# Connector.net
KiCad netlist of a schematic drawn in Altium Designer
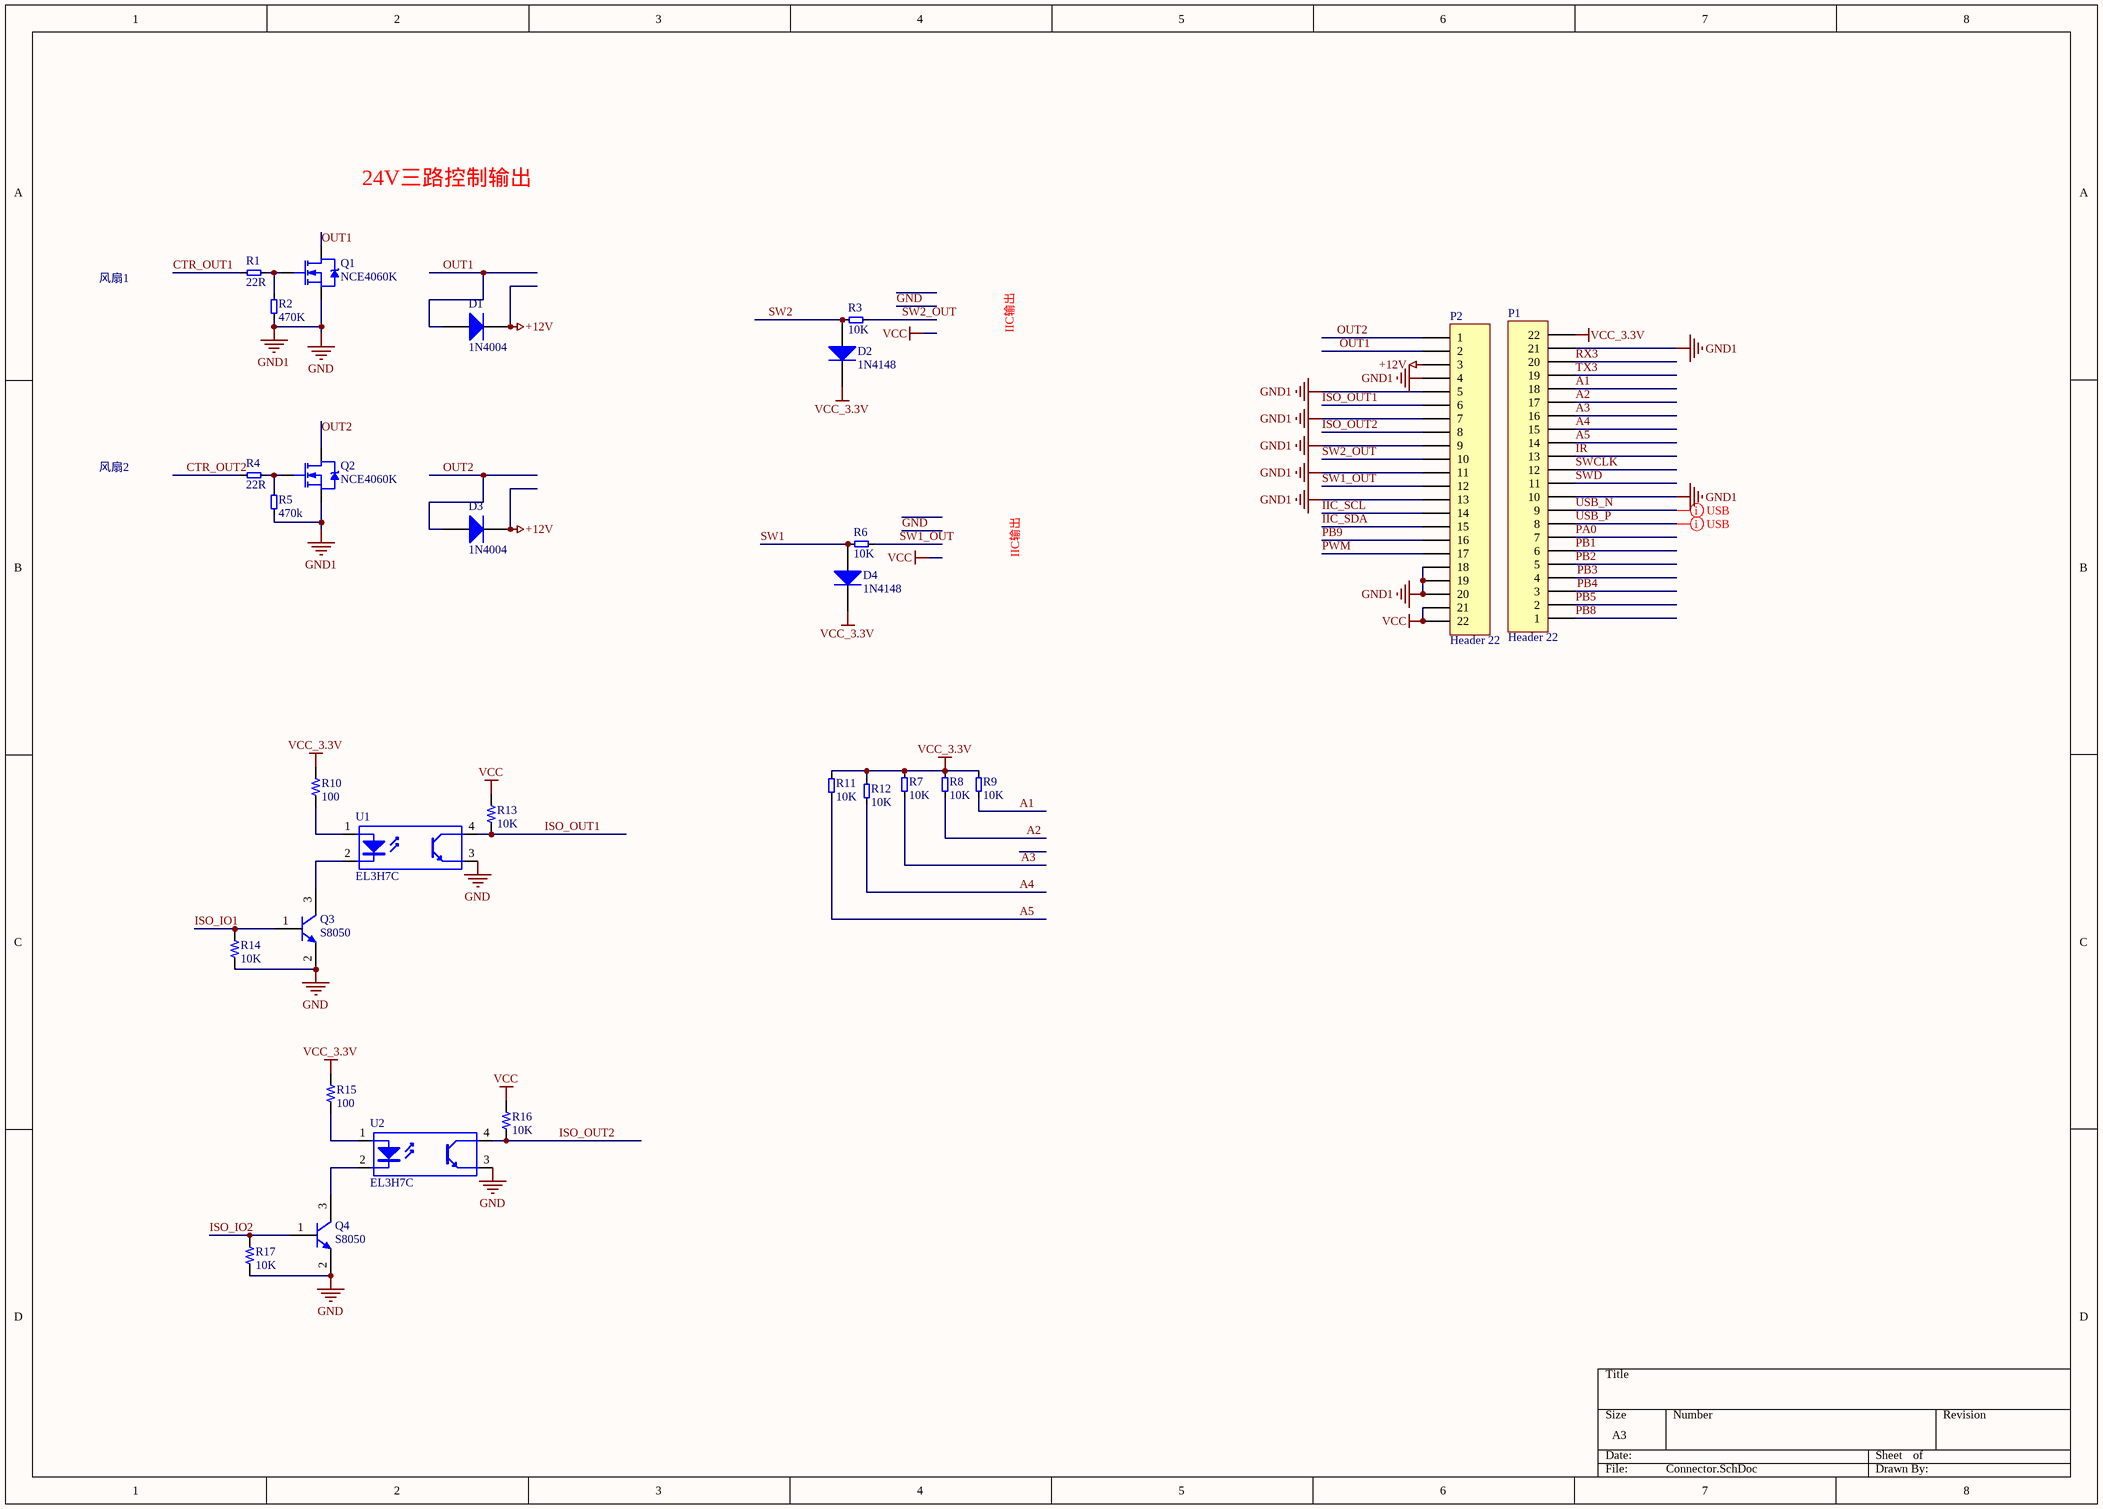
[diagram p0: Connector.SchDoc]

(export (version "E")
  (design (tool "Eeschema 10.0.6"))
  (components
    (comp (ref "D1")
      (value "1N4004")
      (footprint "SMA")
      (description "Default Diode")
      (fields (field (name "PUBLISHER") "Altium Limited"))
      (libsource (lib "SM") (part "Diode_2"))
    )
    (comp (ref "D2")
      (value "1N4148")
      (footprint "sod323")
      (description "Default Diode")
      (fields (field (name "PUBLISHER") "Altium Limited"))
      (libsource (lib "Miscellaneous Devices") (part "Diode"))
    )
    (comp (ref "D3")
      (value "1N4004")
      (footprint "SMA")
      (description "Default Diode")
      (fields (field (name "PUBLISHER") "Altium Limited"))
      (libsource (lib "SM") (part "Diode_2"))
    )
    (comp (ref "D4")
      (value "1N4148")
      (footprint "sod323")
      (description "Default Diode")
      (fields (field (name "PUBLISHER") "Altium Limited"))
      (libsource (lib "Miscellaneous Devices") (part "Diode"))
    )
    (comp (ref "P1")
      (value "Header 22")
      (footprint "pcb_module_a")
      (description "Header, 22-Pin")
      (fields (field (name "PUBLISHER") "Altium Limited"))
      (libsource (lib "Miscellaneous Connectors") (part "Header 22"))
    )
    (comp (ref "P2")
      (value "Header 22")
      (footprint "pcb_module_a")
      (description "Header, 22-Pin")
      (fields (field (name "PUBLISHER") "Altium Limited"))
      (libsource (lib "") (part "Header 22_1"))
    )
    (comp (ref "Q1")
      (value "NCE4060K")
      (footprint "TO-252-3S")
      (description "NMOSFET")
      (libsource (lib "SM") (part "NCE4060K"))
    )
    (comp (ref "Q2")
      (value "NCE4060K")
      (footprint "TO-252-3S")
      (description "NMOSFET")
      (libsource (lib "SM") (part "NCE4060K"))
    )
    (comp (ref "Q3") (value "S8050") (footprint "SOT23-3") (libsource (lib "Schlib1") (part "NPN")))
    (comp (ref "Q4") (value "S8050") (footprint "SOT23-3") (libsource (lib "Schlib1") (part "NPN")))
    (comp (ref "R1")
      (value "22R")
      (footprint "0402R")
      (description "CR85-102J")
      (libsource (lib "SMD电阻") (part "1K"))
    )
    (comp (ref "R2")
      (value "470K")
      (footprint "0402R")
      (description "CR85-102J")
      (libsource (lib "SMD电阻") (part "1K"))
    )
    (comp (ref "R3")
      (value "10K")
      (footprint "0402R")
      (description "CR85-102J")
      (libsource (lib "SMD电阻") (part "1K"))
    )
    (comp (ref "R4")
      (value "22R")
      (footprint "0402R")
      (description "CR85-102J")
      (libsource (lib "SMD电阻") (part "1K"))
    )
    (comp (ref "R5")
      (value "470k")
      (footprint "0402R")
      (description "CR85-102J")
      (libsource (lib "SMD电阻") (part "1K"))
    )
    (comp (ref "R6")
      (value "10K")
      (footprint "0402R")
      (description "CR85-102J")
      (libsource (lib "SMD电阻") (part "1K"))
    )
    (comp (ref "R7")
      (value "10K")
      (footprint "0402R")
      (description "CR85-102J")
      (libsource (lib "SMD电阻") (part "1K"))
    )
    (comp (ref "R8")
      (value "10K")
      (footprint "0402R")
      (description "CR85-102J")
      (libsource (lib "SMD电阻") (part "1K"))
    )
    (comp (ref "R9")
      (value "10K")
      (footprint "0402R")
      (description "CR85-102J")
      (libsource (lib "SMD电阻") (part "1K"))
    )
    (comp (ref "R10")
      (value "100")
      (footprint "0402R")
      (description "R")
      (libsource (lib "JRJ_1") (part "R"))
    )
    (comp (ref "R11")
      (value "10K")
      (footprint "0402R")
      (description "CR85-102J")
      (libsource (lib "SMD电阻") (part "1K"))
    )
    (comp (ref "R12")
      (value "10K")
      (footprint "0402R")
      (description "CR85-102J")
      (libsource (lib "SMD电阻") (part "1K"))
    )
    (comp (ref "R13")
      (value "10K")
      (footprint "0402R")
      (description "R")
      (libsource (lib "JRJ_1") (part "R"))
    )
    (comp (ref "R14")
      (value "10K")
      (footprint "0402R")
      (description "R")
      (libsource (lib "JRJ_1") (part "R"))
    )
    (comp (ref "R15")
      (value "100")
      (footprint "0402R")
      (description "R")
      (libsource (lib "JRJ_1") (part "R"))
    )
    (comp (ref "R16")
      (value "10K")
      (footprint "0402R")
      (description "R")
      (libsource (lib "JRJ_1") (part "R"))
    )
    (comp (ref "R17")
      (value "10K")
      (footprint "0402R")
      (description "R")
      (libsource (lib "JRJ_1") (part "R"))
    )
    (comp (ref "U1")
      (value "EL3H7C")
      (footprint "EL3H7C")
      (description "4-Pin Phototransistor Optocoupler")
      (fields (field (name "PUBLISHER") "Altium Limited"))
      (libsource (lib "Miscellaneous Devices") (part "Optoisolator1"))
    )
    (comp (ref "U2")
      (value "EL3H7C")
      (footprint "EL3H7C")
      (description "4-Pin Phototransistor Optocoupler")
      (fields (field (name "PUBLISHER") "Altium Limited"))
      (libsource (lib "Miscellaneous Devices") (part "Optoisolator1"))
    )
  )
  (nets
    (net (code "1") (name "+12V") (class "Default")
      (node (ref "D1") (pin "2") (pinfunction "K_2") (pintype "passive"))
      (node (ref "D3") (pin "2") (pinfunction "K_2") (pintype "passive"))
      (node (ref "P2") (pin "3") (pinfunction "3_3") (pintype "passive"))
    )
    (net (code "2") (name "/A1") (class "Default")
      (node (ref "P1") (pin "18") (pinfunction "18_18") (pintype "passive"))
      (node (ref "R9") (pin "1") (pinfunction "1_1") (pintype "passive"))
    )
    (net (code "3") (name "/A2") (class "Default")
      (node (ref "P1") (pin "17") (pinfunction "17_17") (pintype "passive"))
      (node (ref "R8") (pin "1") (pinfunction "1_1") (pintype "passive"))
    )
    (net (code "4") (name "/A3") (class "Default")
      (node (ref "P1") (pin "16") (pinfunction "16_16") (pintype "passive"))
      (node (ref "R7") (pin "1") (pinfunction "1_1") (pintype "passive"))
    )
    (net (code "5") (name "/A4") (class "Default")
      (node (ref "P1") (pin "15") (pinfunction "15_15") (pintype "passive"))
      (node (ref "R12") (pin "2") (pinfunction "2_2") (pintype "passive"))
    )
    (net (code "6") (name "/A5") (class "Default")
      (node (ref "P1") (pin "14") (pinfunction "14_14") (pintype "passive"))
      (node (ref "R11") (pin "1") (pinfunction "1_1") (pintype "passive"))
    )
    (net (code "7") (name "/CTR_OUT1") (class "Default")
      (node (ref "R1") (pin "1") (pinfunction "1_1") (pintype "passive"))
    )
    (net (code "8") (name "/CTR_OUT2") (class "Default")
      (node (ref "R4") (pin "1") (pinfunction "1_1") (pintype "passive"))
    )
    (net (code "9") (name "/IIC_SCL") (class "Default")
      (node (ref "P2") (pin "14") (pinfunction "14_14") (pintype "passive"))
    )
    (net (code "10") (name "/IIC_SDA") (class "Default")
      (node (ref "P2") (pin "15") (pinfunction "15_15") (pintype "passive"))
    )
    (net (code "11") (name "/IR") (class "Default")
      (node (ref "P1") (pin "13") (pinfunction "13_13") (pintype "passive"))
    )
    (net (code "12") (name "/ISO_IO1") (class "Default")
      (node (ref "Q3") (pin "1") (pinfunction "B_1") (pintype "passive"))
      (node (ref "R14") (pin "2") (pintype "passive"))
    )
    (net (code "13") (name "/ISO_IO2") (class "Default")
      (node (ref "Q4") (pin "1") (pinfunction "B_1") (pintype "passive"))
      (node (ref "R17") (pin "2") (pintype "passive"))
    )
    (net (code "14") (name "/ISO_OUT1") (class "Default")
      (node (ref "P2") (pin "6") (pinfunction "6_6") (pintype "passive"))
      (node (ref "R13") (pin "1") (pintype "passive"))
      (node (ref "U1") (pin "4") (pinfunction "C_4") (pintype "passive"))
    )
    (net (code "15") (name "/ISO_OUT2") (class "Default")
      (node (ref "P2") (pin "8") (pinfunction "8_8") (pintype "passive"))
      (node (ref "R16") (pin "1") (pintype "passive"))
      (node (ref "U2") (pin "4") (pinfunction "C_4") (pintype "passive"))
    )
    (net (code "16") (name "/OUT1") (class "Default")
      (node (ref "D1") (pin "1") (pinfunction "A_1") (pintype "passive"))
      (node (ref "P2") (pin "2") (pinfunction "2_2") (pintype "passive"))
      (node (ref "Q1") (pin "2") (pinfunction "D_2") (pintype "passive"))
    )
    (net (code "17") (name "/OUT2") (class "Default")
      (node (ref "D3") (pin "1") (pinfunction "A_1") (pintype "passive"))
      (node (ref "P2") (pin "1") (pinfunction "1_1") (pintype "passive"))
      (node (ref "Q2") (pin "2") (pinfunction "D_2") (pintype "passive"))
    )
    (net (code "18") (name "/PA0") (class "Default")
      (node (ref "P1") (pin "7") (pinfunction "7_7") (pintype "passive"))
    )
    (net (code "19") (name "/PB1") (class "Default")
      (node (ref "P1") (pin "6") (pinfunction "6_6") (pintype "passive"))
    )
    (net (code "20") (name "/PB2") (class "Default")
      (node (ref "P1") (pin "5") (pinfunction "5_5") (pintype "passive"))
    )
    (net (code "21") (name "/PB3") (class "Default")
      (node (ref "P1") (pin "4") (pinfunction "4_4") (pintype "passive"))
    )
    (net (code "22") (name "/PB4") (class "Default")
      (node (ref "P1") (pin "3") (pinfunction "3_3") (pintype "passive"))
    )
    (net (code "23") (name "/PB5") (class "Default")
      (node (ref "P1") (pin "2") (pinfunction "2_2") (pintype "passive"))
    )
    (net (code "24") (name "/PB8") (class "Default")
      (node (ref "P1") (pin "1") (pinfunction "1_1") (pintype "passive"))
    )
    (net (code "25") (name "/PB9") (class "Default")
      (node (ref "P2") (pin "16") (pinfunction "16_16") (pintype "passive"))
    )
    (net (code "26") (name "/PWM") (class "Default")
      (node (ref "P2") (pin "17") (pinfunction "17_17") (pintype "passive"))
    )
    (net (code "27") (name "/RX3") (class "Default")
      (node (ref "P1") (pin "20") (pinfunction "20_20") (pintype "passive"))
    )
    (net (code "28") (name "/SW1") (class "Default")
      (node (ref "D4") (pin "A") (pinfunction "A_A") (pintype "passive"))
      (node (ref "R6") (pin "2") (pinfunction "2_2") (pintype "passive"))
    )
    (net (code "29") (name "/SW1_OUT") (class "Default")
      (node (ref "P2") (pin "12") (pinfunction "12_12") (pintype "passive"))
      (node (ref "R6") (pin "1") (pinfunction "1_1") (pintype "passive"))
    )
    (net (code "30") (name "/SW2") (class "Default")
      (node (ref "D2") (pin "A") (pinfunction "A_A") (pintype "passive"))
      (node (ref "R3") (pin "2") (pinfunction "2_2") (pintype "passive"))
    )
    (net (code "31") (name "/SW2_OUT") (class "Default")
      (node (ref "P2") (pin "10") (pinfunction "10_10") (pintype "passive"))
      (node (ref "R3") (pin "1") (pinfunction "1_1") (pintype "passive"))
    )
    (net (code "32") (name "/SWCLK") (class "Default")
      (node (ref "P1") (pin "12") (pinfunction "12_12") (pintype "passive"))
    )
    (net (code "33") (name "/SWD") (class "Default")
      (node (ref "P1") (pin "11") (pinfunction "11_11") (pintype "passive"))
    )
    (net (code "34") (name "/TX3") (class "Default")
      (node (ref "P1") (pin "19") (pinfunction "19_19") (pintype "passive"))
    )
    (net (code "35") (name "/USB_N") (class "Default")
      (node (ref "P1") (pin "9") (pinfunction "9_9") (pintype "passive"))
    )
    (net (code "36") (name "/USB_P") (class "Default")
      (node (ref "P1") (pin "8") (pinfunction "8_8") (pintype "passive"))
    )
    (net (code "37") (name "GND") (class "Default")
      (node (ref "P1") (pin "10") (pinfunction "10_10") (pintype "passive"))
      (node (ref "P1") (pin "21") (pinfunction "21_21") (pintype "passive"))
      (node (ref "P2") (pin "11") (pinfunction "11_11") (pintype "passive"))
      (node (ref "P2") (pin "13") (pinfunction "13_13") (pintype "passive"))
      (node (ref "P2") (pin "18") (pinfunction "18_18") (pintype "passive"))
      (node (ref "P2") (pin "19") (pinfunction "19_19") (pintype "passive"))
      (node (ref "P2") (pin "20") (pinfunction "20_20") (pintype "passive"))
      (node (ref "P2") (pin "4") (pinfunction "4_4") (pintype "passive"))
      (node (ref "P2") (pin "5") (pinfunction "5_5") (pintype "passive"))
      (node (ref "P2") (pin "7") (pinfunction "7_7") (pintype "passive"))
      (node (ref "P2") (pin "9") (pinfunction "9_9") (pintype "passive"))
      (node (ref "Q1") (pin "3") (pinfunction "S_3") (pintype "passive"))
      (node (ref "Q2") (pin "3") (pinfunction "S_3") (pintype "passive"))
      (node (ref "Q3") (pin "2") (pinfunction "E_2") (pintype "passive"))
      (node (ref "Q4") (pin "2") (pinfunction "E_2") (pintype "passive"))
      (node (ref "R14") (pin "1") (pintype "passive"))
      (node (ref "R17") (pin "1") (pintype "passive"))
      (node (ref "R2") (pin "1") (pinfunction "1_1") (pintype "passive"))
      (node (ref "R5") (pin "1") (pinfunction "1_1") (pintype "passive"))
      (node (ref "U1") (pin "3") (pinfunction "E_3") (pintype "passive"))
      (node (ref "U2") (pin "3") (pinfunction "E_3") (pintype "passive"))
    )
    (net (code "38") (name "Net-(Q1-G)") (class "Default")
      (node (ref "Q1") (pin "1") (pinfunction "G_1") (pintype "passive"))
      (node (ref "R1") (pin "2") (pinfunction "2_2") (pintype "passive"))
      (node (ref "R2") (pin "2") (pinfunction "2_2") (pintype "passive"))
    )
    (net (code "39") (name "Net-(Q2-G)") (class "Default")
      (node (ref "Q2") (pin "1") (pinfunction "G_1") (pintype "passive"))
      (node (ref "R4") (pin "2") (pinfunction "2_2") (pintype "passive"))
      (node (ref "R5") (pin "2") (pinfunction "2_2") (pintype "passive"))
    )
    (net (code "40") (name "Net-(Q3-C)") (class "Default")
      (node (ref "Q3") (pin "3") (pinfunction "C_3") (pintype "passive"))
      (node (ref "U1") (pin "2") (pinfunction "K_2") (pintype "passive"))
    )
    (net (code "41") (name "Net-(Q4-C)") (class "Default")
      (node (ref "Q4") (pin "3") (pinfunction "C_3") (pintype "passive"))
      (node (ref "U2") (pin "2") (pinfunction "K_2") (pintype "passive"))
    )
    (net (code "42") (name "Net-(U1-A)") (class "Default")
      (node (ref "R10") (pin "1") (pintype "passive"))
      (node (ref "U1") (pin "1") (pinfunction "A_1") (pintype "passive"))
    )
    (net (code "43") (name "Net-(U2-A)") (class "Default")
      (node (ref "R15") (pin "1") (pintype "passive"))
      (node (ref "U2") (pin "1") (pinfunction "A_1") (pintype "passive"))
    )
    (net (code "44") (name "VCC") (class "Default")
      (node (ref "P2") (pin "21") (pinfunction "21_21") (pintype "passive"))
      (node (ref "P2") (pin "22") (pinfunction "22_22") (pintype "passive"))
      (node (ref "R13") (pin "2") (pintype "passive"))
      (node (ref "R16") (pin "2") (pintype "passive"))
    )
    (net (code "45") (name "VCC_3.3V") (class "Default")
      (node (ref "D2") (pin "K") (pinfunction "K_K") (pintype "passive"))
      (node (ref "D4") (pin "K") (pinfunction "K_K") (pintype "passive"))
      (node (ref "P1") (pin "22") (pinfunction "22_22") (pintype "passive"))
      (node (ref "R10") (pin "2") (pintype "passive"))
      (node (ref "R11") (pin "2") (pinfunction "2_2") (pintype "passive"))
      (node (ref "R12") (pin "1") (pinfunction "1_1") (pintype "passive"))
      (node (ref "R15") (pin "2") (pintype "passive"))
      (node (ref "R7") (pin "2") (pinfunction "2_2") (pintype "passive"))
      (node (ref "R8") (pin "2") (pinfunction "2_2") (pintype "passive"))
      (node (ref "R9") (pin "2") (pinfunction "2_2") (pintype "passive"))
    )
  )
)
